# Buck_Converter.net
KiCad netlist of a schematic drawn in Altium Designer
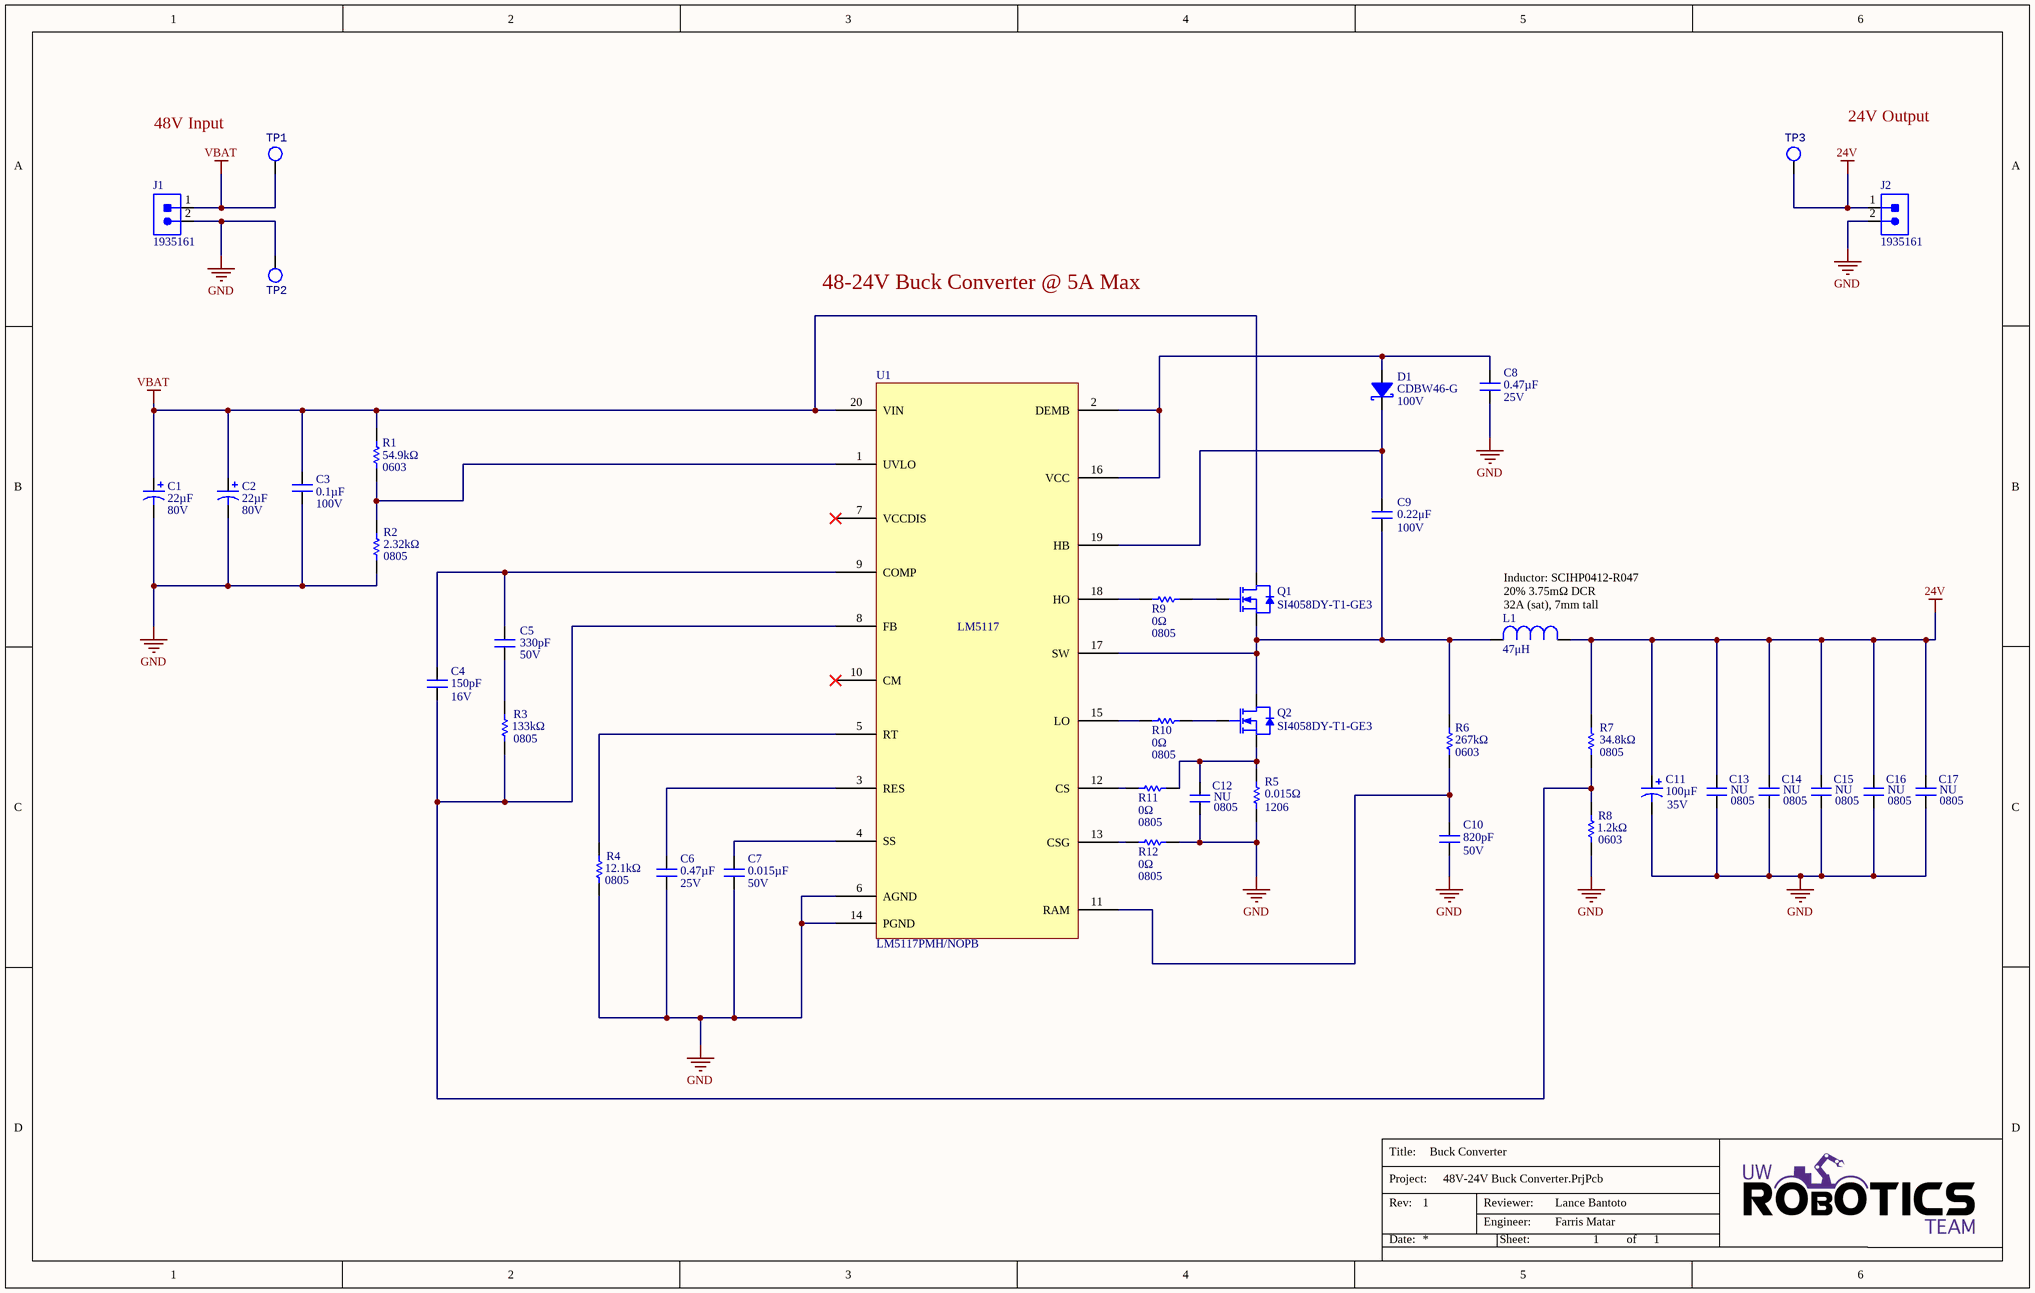
[diagram p0: Buck Converter.SchDoc]

(export (version "E")
  (design (tool "Eeschema 10.0.6"))
  (components
    (comp (ref "C1")
      (value "22µF")
      (footprint "RADIAL_PANASONIC_F")
      (description "CAP ALUM POLY 22UF 20% 80V SMD")
      (fields (field (name "VOLTAGE RATING") "80V") (field (name "Comment") "CAP_22uF_80V_ALUM"))
      (libsource (lib "UWRT_Schematic_Library_2020") (part "CAP_22uF_80V_ALUM"))
    )
    (comp (ref "C2")
      (value "22µF")
      (footprint "RADIAL_PANASONIC_F")
      (description "CAP ALUM POLY 22UF 20% 80V SMD")
      (fields (field (name "VOLTAGE RATING") "80V") (field (name "Comment") "CAP_22uF_80V_ALUM"))
      (libsource (lib "UWRT_Schematic_Library_2020") (part "CAP_22uF_80V_ALUM"))
    )
    (comp (ref "C3")
      (value "0.1µF")
      (footprint "CAP0805")
      (description "CAP CER 0.1UF 100V X7R 0805")
      (fields (field (name "VOLTAGE RATING") "100V") (field (name "Comment") "CAP_0.1uF_100V_0805"))
      (libsource (lib "UWRT_Schematic_Library_2020") (part "CAP_0.1uF_100V_0805"))
    )
    (comp (ref "C4")
      (value "150pF")
      (footprint "CAP0805")
      (description "CAP CER 150PF 16V X7R 0805")
      (fields (field (name "VOLTAGE RATING") "16V") (field (name "Comment") "CAP_150pF_16V_0805"))
      (libsource (lib "UWRT_Schematic_Library_2020") (part "CAP_150pF_16V_0805"))
    )
    (comp (ref "C5")
      (value "330pF")
      (footprint "CAP0805")
      (description "CAP CER 330PF 50V C0G/NPO 0805")
      (fields (field (name "VOLTAGE RATING") "50V") (field (name "Comment") "CAP_330pF_50V_0805"))
      (libsource (lib "UWRT_Schematic_Library_2020") (part "CAP_330pF_50V_0805"))
    )
    (comp (ref "C6")
      (value "0.47µF")
      (footprint "CAP0805")
      (description "CAP CER 0.47UF 25V X5R 0805")
      (fields (field (name "VOLTAGE RATING") "25V") (field (name "Comment") "CAP_0.47uF_25V_0805"))
      (libsource (lib "UWRT_Schematic_Library_2020") (part "CAP_0.47uF_25V_0805"))
    )
    (comp (ref "C7")
      (value "0.015µF")
      (footprint "CAP0805")
      (description "CAP CER 0.015UF 50V C0G 0805")
      (fields (field (name "VOLTAGE RATING") "50V") (field (name "Comment") "CAP_0.015uF_50V_0805"))
      (libsource (lib "UWRT_Schematic_Library_2020") (part "CAP_0.015uF_50V_0805"))
    )
    (comp (ref "C8")
      (value "0.47µF")
      (footprint "CAP0805")
      (description "CAP CER 0.47UF 25V X5R 0805")
      (fields (field (name "VOLTAGE RATING") "25V") (field (name "Comment") "CAP_0.47uF_25V_0805"))
      (libsource (lib "UWRT_Schematic_Library_2020") (part "CAP_0.47uF_25V_0805"))
    )
    (comp (ref "C9")
      (value "0.22μF")
      (footprint "CAP2012")
      (description "CAP CER 0.22UF 100V X7R 0805")
      (fields (field (name "VOLTAGE RATING") "100V") (field (name "Comment") "CAP_0.22uF_100V_0805"))
      (libsource (lib "UWRT_Schematic_Library_2020") (part "CAP_0.22uF_100V_0805"))
    )
    (comp (ref "C10")
      (value "820pF")
      (footprint "CAP0805")
      (description "CAP CER 820PF 50V C0G/NP0 0805")
      (fields (field (name "VOLTAGE RATING") "50V") (field (name "Comment") "CAP_820pF_50V_0805"))
      (libsource (lib "UWRT_Schematic_Library_2020") (part "CAP_820pF_50V_0805"))
    )
    (comp (ref "C11")
      (value "100µF")
      (footprint "RADIAL_CORNELL_D")
      (description "CAP ALUM 100UF 20% 35V SMD")
      (fields (field (name "VOLTAGE RATING") "35V") (field (name "Comment") "CAP_100uF_35V_ALUM"))
      (libsource (lib "UWRT_Schematic_Library_2020") (part "CAP_100uF_35V_ALUM"))
    )
    (comp (ref "C12")
      (value "NU")
      (footprint "CAP0805")
      (description "PLACEHOLDER CAPACITOR 0805")
      (fields (field (name "PACKAGE/FOOTPRINT") "0805") (field (name "Comment") "CAP_NU_0805"))
      (libsource (lib "UWRT_Schematic_Library_2020") (part "CAP_NU_0805"))
    )
    (comp (ref "C13")
      (value "NU")
      (footprint "CAP0805")
      (description "PLACEHOLDER CAPACITOR 0805")
      (fields (field (name "PACKAGE/FOOTPRINT") "0805") (field (name "Comment") "CAP_NU_0805"))
      (libsource (lib "UWRT_Schematic_Library_2020") (part "CAP_NU_0805"))
    )
    (comp (ref "C14")
      (value "NU")
      (footprint "CAP0805")
      (description "PLACEHOLDER CAPACITOR 0805")
      (fields (field (name "PACKAGE/FOOTPRINT") "0805") (field (name "Comment") "CAP_NU_0805"))
      (libsource (lib "UWRT_Schematic_Library_2020") (part "CAP_NU_0805"))
    )
    (comp (ref "C15")
      (value "NU")
      (footprint "CAP0805")
      (description "PLACEHOLDER CAPACITOR 0805")
      (fields (field (name "PACKAGE/FOOTPRINT") "0805") (field (name "Comment") "CAP_NU_0805"))
      (libsource (lib "UWRT_Schematic_Library_2020") (part "CAP_NU_0805"))
    )
    (comp (ref "C16")
      (value "NU")
      (footprint "CAP0805")
      (description "PLACEHOLDER CAPACITOR 0805")
      (fields (field (name "PACKAGE/FOOTPRINT") "0805") (field (name "Comment") "CAP_NU_0805"))
      (libsource (lib "UWRT_Schematic_Library_2020") (part "CAP_NU_0805"))
    )
    (comp (ref "C17")
      (value "NU")
      (footprint "CAP0805")
      (description "PLACEHOLDER CAPACITOR 0805")
      (fields (field (name "PACKAGE/FOOTPRINT") "0805") (field (name "Comment") "CAP_NU_0805"))
      (libsource (lib "UWRT_Schematic_Library_2020") (part "CAP_NU_0805"))
    )
    (comp (ref "D1")
      (value "DIO_SCHOTTKY_100V_150mA")
      (footprint "SOD-123_FLAT")
      (description "DIODE SCHOTTKY 100V 150MA SOD123")
      (fields (field (name "MANUFACTURER PART NUMBER 1") "CDBW46-G") (field (name "VR (MAX)") "100V"))
      (libsource (lib "UWRT_Schematic_Library_2020") (part "DIO_SCHOTTKY_100V_150mA"))
    )
    (comp (ref "J1")
      (value "CON_2POS_SCREW_TERM")
      (footprint "1935161")
      (description "TERM BLK 2POS SIDE ENTRY 5MM")
      (fields (field (name "MANUFACTURER PART NUMBER 1") "1935161"))
      (libsource (lib "UWRT_Schematic_Library_2020") (part "CON_2POS_SCREW_TERM"))
    )
    (comp (ref "J2")
      (value "CON_2POS_SCREW_TERM")
      (footprint "1935161")
      (description "TERM BLK 2POS SIDE ENTRY 5MM")
      (fields (field (name "MANUFACTURER PART NUMBER 1") "1935161"))
      (libsource (lib "") (part "CON_2POS_SCREW_TERM_1"))
    )
    (comp (ref "L1")
      (value "IND_47uH_13.0A")
      (footprint "IND_SIGNAL_SCIHP0412-R047")
      (description "FIXED IND 47NH 13A SMD")
      (fields (field (name "INDUCTANCE") "47μH"))
      (libsource (lib "UWRT_Schematic_Library_2020") (part "IND_47uH_13.0A"))
    )
    (comp (ref "Q1")
      (value "NMOS_100V_10.3A")
      (footprint "8-SOIC_NMOS")
      (description "MOSFET N-CH 100V 10.3A 8SOIC")
      (fields (field (name "MANUFACTURER PART NUMBER 1") "SI4058DY-T1-GE3"))
      (libsource (lib "UWRT_Schematic_Library_2020") (part "NMOS_100V_10.3A"))
    )
    (comp (ref "Q2")
      (value "NMOS_100V_10.3A")
      (footprint "8-SOIC_NMOS")
      (description "MOSFET N-CH 100V 10.3A 8SOIC")
      (fields (field (name "MANUFACTURER PART NUMBER 1") "SI4058DY-T1-GE3"))
      (libsource (lib "UWRT_Schematic_Library_2020") (part "NMOS_100V_10.3A"))
    )
    (comp (ref "R1")
      (value "54.9kΩ")
      (footprint "RES0603")
      (description "RES SMD 54.9K OHM 1% 1/10W 0603")
      (fields (field (name "PACKAGE/FOOTPRINT") "0603") (field (name "Comment") "RES_54.9kΩ_0603_1%"))
      (libsource (lib "UWRT_Schematic_Library_2020") (part "RES_54.9kΩ_0603_1%"))
    )
    (comp (ref "R2")
      (value "2.32kΩ")
      (footprint "RES0805")
      (description "RES 2.32K OHM 1% 1/4W 0805")
      (fields (field (name "PACKAGE/FOOTPRINT") "0805") (field (name "Comment") "RES_2.32kΩ_0805_1%"))
      (libsource (lib "UWRT_Schematic_Library_2020") (part "RES_2.32kΩ_0805_1%"))
    )
    (comp (ref "R3")
      (value "133kΩ")
      (footprint "RES0805")
      (description "RES SMD 133K OHM 1% 1/8W 0805")
      (fields (field (name "PACKAGE/FOOTPRINT") "0805") (field (name "Comment") "RES_133kΩ_0805_1%"))
      (libsource (lib "UWRT_Schematic_Library_2020") (part "RES_133kΩ_0805_1%"))
    )
    (comp (ref "R4")
      (value "12.1kΩ")
      (footprint "RES0805")
      (description "RES 12.1K OHM 1% 1/4W 0805")
      (fields (field (name "PACKAGE/FOOTPRINT") "0805") (field (name "Comment") "RES_12.1kΩ_0805_1%"))
      (libsource (lib "UWRT_Schematic_Library_2020") (part "RES_12.1kΩ_0805_1%"))
    )
    (comp (ref "R5")
      (value "0.015Ω")
      (footprint "RES1206")
      (description "RES 0.015 OHM 1% 1/2W 1206")
      (fields (field (name "PACKAGE/FOOTPRINT") "1206") (field (name "Comment") "RES_0.015Ω_1206_1%"))
      (libsource (lib "UWRT_Schematic_Library_2020") (part "RES_0.015Ω_1206_1%"))
    )
    (comp (ref "R6")
      (value "267kΩ")
      (footprint "RES0603")
      (description "RES SMD 267K OHM 1% 1/10W 0603")
      (fields (field (name "PACKAGE/FOOTPRINT") "0603") (field (name "Comment") "RES_267kΩ_0603_1%"))
      (libsource (lib "UWRT_Schematic_Library_2020") (part "RES_267kΩ_0603_1%"))
    )
    (comp (ref "R7")
      (value "34.8kΩ")
      (footprint "RES0805")
      (description "RES 34.8K OHM 1% 1/8W 0805")
      (fields (field (name "PACKAGE/FOOTPRINT") "0805") (field (name "Comment") "RES_34.8kΩ_0805_1%"))
      (libsource (lib "UWRT_Schematic_Library_2020") (part "RES_34.8kΩ_0805_1%"))
    )
    (comp (ref "R8")
      (value "1.2kΩ")
      (footprint "RES0603")
      (description "RES SMD 1.2K OHM 1% 1/10W 0603")
      (fields (field (name "PACKAGE/FOOTPRINT") "0603") (field (name "Comment") "RES_1.2kΩ_0603_1%"))
      (libsource (lib "UWRT_Schematic_Library_2020") (part "RES_1.2kΩ_0603_1%"))
    )
    (comp (ref "R9")
      (value "0Ω")
      (footprint "RES0805")
      (description "RES 0 OHM JUMPER 1/8W 0805")
      (fields
        (field (name "PACKAGE/FOOTPRINT") "0805")
        (field (name "LCSC PART #") "C17477")
        (field (name "Comment") "RES_0Ω_0805")
      )
      (libsource (lib "UWRT_Schematic_Library_2020") (part "RES_0Ω_0805"))
    )
    (comp (ref "R10")
      (value "0Ω")
      (footprint "RES0805")
      (description "RES 0 OHM JUMPER 1/8W 0805")
      (fields
        (field (name "PACKAGE/FOOTPRINT") "0805")
        (field (name "LCSC PART #") "C17477")
        (field (name "Comment") "RES_0Ω_0805")
      )
      (libsource (lib "UWRT_Schematic_Library_2020") (part "RES_0Ω_0805"))
    )
    (comp (ref "R11")
      (value "0Ω")
      (footprint "RES0805")
      (description "RES 0 OHM JUMPER 1/8W 0805")
      (fields
        (field (name "PACKAGE/FOOTPRINT") "0805")
        (field (name "LCSC PART #") "C17477")
        (field (name "Comment") "RES_0Ω_0805")
      )
      (libsource (lib "UWRT_Schematic_Library_2020") (part "RES_0Ω_0805"))
    )
    (comp (ref "R12")
      (value "0Ω")
      (footprint "RES0805")
      (description "RES 0 OHM JUMPER 1/8W 0805")
      (fields
        (field (name "PACKAGE/FOOTPRINT") "0805")
        (field (name "LCSC PART #") "C17477")
        (field (name "Comment") "RES_0Ω_0805")
      )
      (libsource (lib "UWRT_Schematic_Library_2020") (part "RES_0Ω_0805"))
    )
    (comp (ref "TP1")
      (value "TESTPOINT_LOOP")
      (footprint "TESTPOINT_LOOP")
      (description "TESTPOINT THRUHOLE")
      (libsource (lib "UWRT_Schematic_Library_2020") (part "TESTPOINT_LOOP"))
    )
    (comp (ref "TP2")
      (value "TESTPOINT_LOOP")
      (footprint "TESTPOINT_LOOP")
      (description "TESTPOINT THRUHOLE")
      (libsource (lib "UWRT_Schematic_Library_2020") (part "TESTPOINT_LOOP"))
    )
    (comp (ref "TP3")
      (value "TESTPOINT_LOOP")
      (footprint "TESTPOINT_LOOP")
      (description "TESTPOINT THRUHOLE")
      (libsource (lib "UWRT_Schematic_Library_2020") (part "TESTPOINT_LOOP"))
    )
    (comp (ref "U1")
      (value "BUCK_LM5117PWP")
      (footprint "HTSSOP")
      (description "IC REG CTRLR BUCK 20TSSOP")
      (fields (field (name "MANUFACTURER PART NUMBER 1") "LM5117PMH/NOPB"))
      (libsource (lib "UWRT_Schematic_Library_2020") (part "BUCK_LM5117PWP"))
    )
  )
  (nets
    (net (code "1") (name "24V") (class "Default")
      (node (ref "C11") (pin "1") (pinfunction "1_1") (pintype "passive"))
      (node (ref "C13") (pin "2") (pinfunction "2_2") (pintype "passive"))
      (node (ref "C14") (pin "2") (pinfunction "2_2") (pintype "passive"))
      (node (ref "C15") (pin "2") (pinfunction "2_2") (pintype "passive"))
      (node (ref "C16") (pin "2") (pinfunction "2_2") (pintype "passive"))
      (node (ref "C17") (pin "2") (pinfunction "2_2") (pintype "passive"))
      (node (ref "J2") (pin "1") (pinfunction "1_1") (pintype "passive"))
      (node (ref "L1") (pin "1") (pinfunction "1_1") (pintype "passive"))
      (node (ref "R7") (pin "2") (pinfunction "2_2") (pintype "passive"))
      (node (ref "TP3") (pin "1") (pintype "passive"))
    )
    (net (code "2") (name "GND") (class "Default")
      (node (ref "C1") (pin "2") (pinfunction "2_2") (pintype "passive"))
      (node (ref "C10") (pin "1") (pinfunction "1_1") (pintype "passive"))
      (node (ref "C11") (pin "2") (pinfunction "2_2") (pintype "passive"))
      (node (ref "C12") (pin "1") (pinfunction "1_1") (pintype "passive"))
      (node (ref "C13") (pin "1") (pinfunction "1_1") (pintype "passive"))
      (node (ref "C14") (pin "1") (pinfunction "1_1") (pintype "passive"))
      (node (ref "C15") (pin "1") (pinfunction "1_1") (pintype "passive"))
      (node (ref "C16") (pin "1") (pinfunction "1_1") (pintype "passive"))
      (node (ref "C17") (pin "1") (pinfunction "1_1") (pintype "passive"))
      (node (ref "C2") (pin "2") (pinfunction "2_2") (pintype "passive"))
      (node (ref "C3") (pin "1") (pinfunction "1_1") (pintype "passive"))
      (node (ref "C6") (pin "1") (pinfunction "1_1") (pintype "passive"))
      (node (ref "C7") (pin "1") (pinfunction "1_1") (pintype "passive"))
      (node (ref "C8") (pin "1") (pinfunction "1_1") (pintype "passive"))
      (node (ref "J1") (pin "2") (pinfunction "2_2") (pintype "passive"))
      (node (ref "J2") (pin "2") (pinfunction "2_2") (pintype "passive"))
      (node (ref "R12") (pin "2") (pinfunction "2_2") (pintype "passive"))
      (node (ref "R2") (pin "1") (pinfunction "1_1") (pintype "passive"))
      (node (ref "R4") (pin "1") (pinfunction "1_1") (pintype "passive"))
      (node (ref "R5") (pin "1") (pinfunction "1_1") (pintype "passive"))
      (node (ref "R8") (pin "1") (pinfunction "1_1") (pintype "passive"))
      (node (ref "TP2") (pin "1") (pintype "passive"))
      (node (ref "U1") (pin "14") (pinfunction "PGND_14") (pintype "passive"))
      (node (ref "U1") (pin "6") (pinfunction "AGND_6") (pintype "passive"))
    )
    (net (code "3") (name "Net-(C5-Pad1)") (class "Default")
      (node (ref "C5") (pin "1") (pinfunction "1_1") (pintype "passive"))
      (node (ref "R3") (pin "2") (pinfunction "2_2") (pintype "passive"))
    )
    (net (code "4") (name "Net-(D1-Anode)") (class "Default")
      (node (ref "C8") (pin "2") (pinfunction "2_2") (pintype "passive"))
      (node (ref "D1") (pin "1") (pinfunction "Anode_1") (pintype "passive"))
      (node (ref "U1") (pin "16") (pinfunction "VCC_16") (pintype "passive"))
      (node (ref "U1") (pin "2") (pinfunction "DEMB_2") (pintype "passive"))
    )
    (net (code "5") (name "Net-(D1-Cathode)") (class "Default")
      (node (ref "C9") (pin "2") (pinfunction "2_2") (pintype "passive"))
      (node (ref "D1") (pin "2") (pinfunction "Cathode_2") (pintype "passive"))
      (node (ref "U1") (pin "19") (pinfunction "HB_19") (pintype "passive"))
    )
    (net (code "6") (name "Net-(Q1-Gate)") (class "Default")
      (node (ref "Q1") (pin "1") (pinfunction "Gate_1") (pintype "passive"))
      (node (ref "R9") (pin "2") (pinfunction "2_2") (pintype "passive"))
    )
    (net (code "7") (name "Net-(Q1-Source)") (class "Default")
      (node (ref "C9") (pin "1") (pinfunction "1_1") (pintype "passive"))
      (node (ref "L1") (pin "2") (pinfunction "2_2") (pintype "passive"))
      (node (ref "Q1") (pin "2") (pinfunction "Source_2") (pintype "passive"))
      (node (ref "Q2") (pin "3") (pinfunction "Drain_3") (pintype "passive"))
      (node (ref "R6") (pin "2") (pinfunction "2_2") (pintype "passive"))
      (node (ref "U1") (pin "17") (pinfunction "SW_17") (pintype "passive"))
    )
    (net (code "8") (name "Net-(Q2-Gate)") (class "Default")
      (node (ref "Q2") (pin "1") (pinfunction "Gate_1") (pintype "passive"))
      (node (ref "R10") (pin "2") (pinfunction "2_2") (pintype "passive"))
    )
    (net (code "9") (name "Net-(Q2-Source)") (class "Default")
      (node (ref "C12") (pin "2") (pinfunction "2_2") (pintype "passive"))
      (node (ref "Q2") (pin "2") (pinfunction "Source_2") (pintype "passive"))
      (node (ref "R11") (pin "2") (pinfunction "2_2") (pintype "passive"))
      (node (ref "R5") (pin "2") (pinfunction "2_2") (pintype "passive"))
    )
    (net (code "10") (name "Net-(U1-COMP)") (class "Default")
      (node (ref "C4") (pin "2") (pinfunction "2_2") (pintype "passive"))
      (node (ref "C5") (pin "2") (pinfunction "2_2") (pintype "passive"))
      (node (ref "U1") (pin "9") (pinfunction "COMP_9") (pintype "passive"))
    )
    (net (code "11") (name "Net-(U1-CS)") (class "Default")
      (node (ref "R11") (pin "1") (pinfunction "1_1") (pintype "passive"))
      (node (ref "U1") (pin "12") (pinfunction "CS_12") (pintype "passive"))
    )
    (net (code "12") (name "Net-(U1-CSG)") (class "Default")
      (node (ref "R12") (pin "1") (pinfunction "1_1") (pintype "passive"))
      (node (ref "U1") (pin "13") (pinfunction "CSG_13") (pintype "passive"))
    )
    (net (code "13") (name "Net-(U1-FB)") (class "Default")
      (node (ref "C4") (pin "1") (pinfunction "1_1") (pintype "passive"))
      (node (ref "R3") (pin "1") (pinfunction "1_1") (pintype "passive"))
      (node (ref "R7") (pin "1") (pinfunction "1_1") (pintype "passive"))
      (node (ref "R8") (pin "2") (pinfunction "2_2") (pintype "passive"))
      (node (ref "U1") (pin "8") (pinfunction "FB_8") (pintype "passive"))
    )
    (net (code "14") (name "Net-(U1-HO)") (class "Default")
      (node (ref "R9") (pin "1") (pinfunction "1_1") (pintype "passive"))
      (node (ref "U1") (pin "18") (pinfunction "HO_18") (pintype "passive"))
    )
    (net (code "15") (name "Net-(U1-LO)") (class "Default")
      (node (ref "R10") (pin "1") (pinfunction "1_1") (pintype "passive"))
      (node (ref "U1") (pin "15") (pinfunction "LO_15") (pintype "passive"))
    )
    (net (code "16") (name "Net-(U1-RAM)") (class "Default")
      (node (ref "C10") (pin "2") (pinfunction "2_2") (pintype "passive"))
      (node (ref "R6") (pin "1") (pinfunction "1_1") (pintype "passive"))
      (node (ref "U1") (pin "11") (pinfunction "RAM_11") (pintype "passive"))
    )
    (net (code "17") (name "Net-(U1-RES)") (class "Default")
      (node (ref "C6") (pin "2") (pinfunction "2_2") (pintype "passive"))
      (node (ref "U1") (pin "3") (pinfunction "RES_3") (pintype "passive"))
    )
    (net (code "18") (name "Net-(U1-RT)") (class "Default")
      (node (ref "R4") (pin "2") (pinfunction "2_2") (pintype "passive"))
      (node (ref "U1") (pin "5") (pinfunction "RT_5") (pintype "passive"))
    )
    (net (code "19") (name "Net-(U1-SS)") (class "Default")
      (node (ref "C7") (pin "2") (pinfunction "2_2") (pintype "passive"))
      (node (ref "U1") (pin "4") (pinfunction "SS_4") (pintype "passive"))
    )
    (net (code "20") (name "Net-(U1-UVLO)") (class "Default")
      (node (ref "R1") (pin "1") (pinfunction "1_1") (pintype "passive"))
      (node (ref "R2") (pin "2") (pinfunction "2_2") (pintype "passive"))
      (node (ref "U1") (pin "1") (pinfunction "UVLO_1") (pintype "passive"))
    )
    (net (code "21") (name "VBAT") (class "Default")
      (node (ref "C1") (pin "1") (pinfunction "1_1") (pintype "passive"))
      (node (ref "C2") (pin "1") (pinfunction "1_1") (pintype "passive"))
      (node (ref "C3") (pin "2") (pinfunction "2_2") (pintype "passive"))
      (node (ref "J1") (pin "1") (pinfunction "1_1") (pintype "passive"))
      (node (ref "Q1") (pin "3") (pinfunction "Drain_3") (pintype "passive"))
      (node (ref "R1") (pin "2") (pinfunction "2_2") (pintype "passive"))
      (node (ref "TP1") (pin "1") (pintype "passive"))
      (node (ref "U1") (pin "20") (pinfunction "VIN_20") (pintype "passive"))
    )
    (net (code "22") (name "unconnected-(U1-CM-Pad10)") (class "Default")
      (node (ref "U1") (pin "10") (pinfunction "CM_10") (pintype "passive+no_connect"))
    )
    (net (code "23") (name "unconnected-(U1-VCCDIS-Pad7)") (class "Default")
      (node (ref "U1") (pin "7") (pinfunction "VCCDIS_7") (pintype "passive+no_connect"))
    )
  )
)
